# schematic.net
KiCad netlist of a schematic drawn in Altium Designer
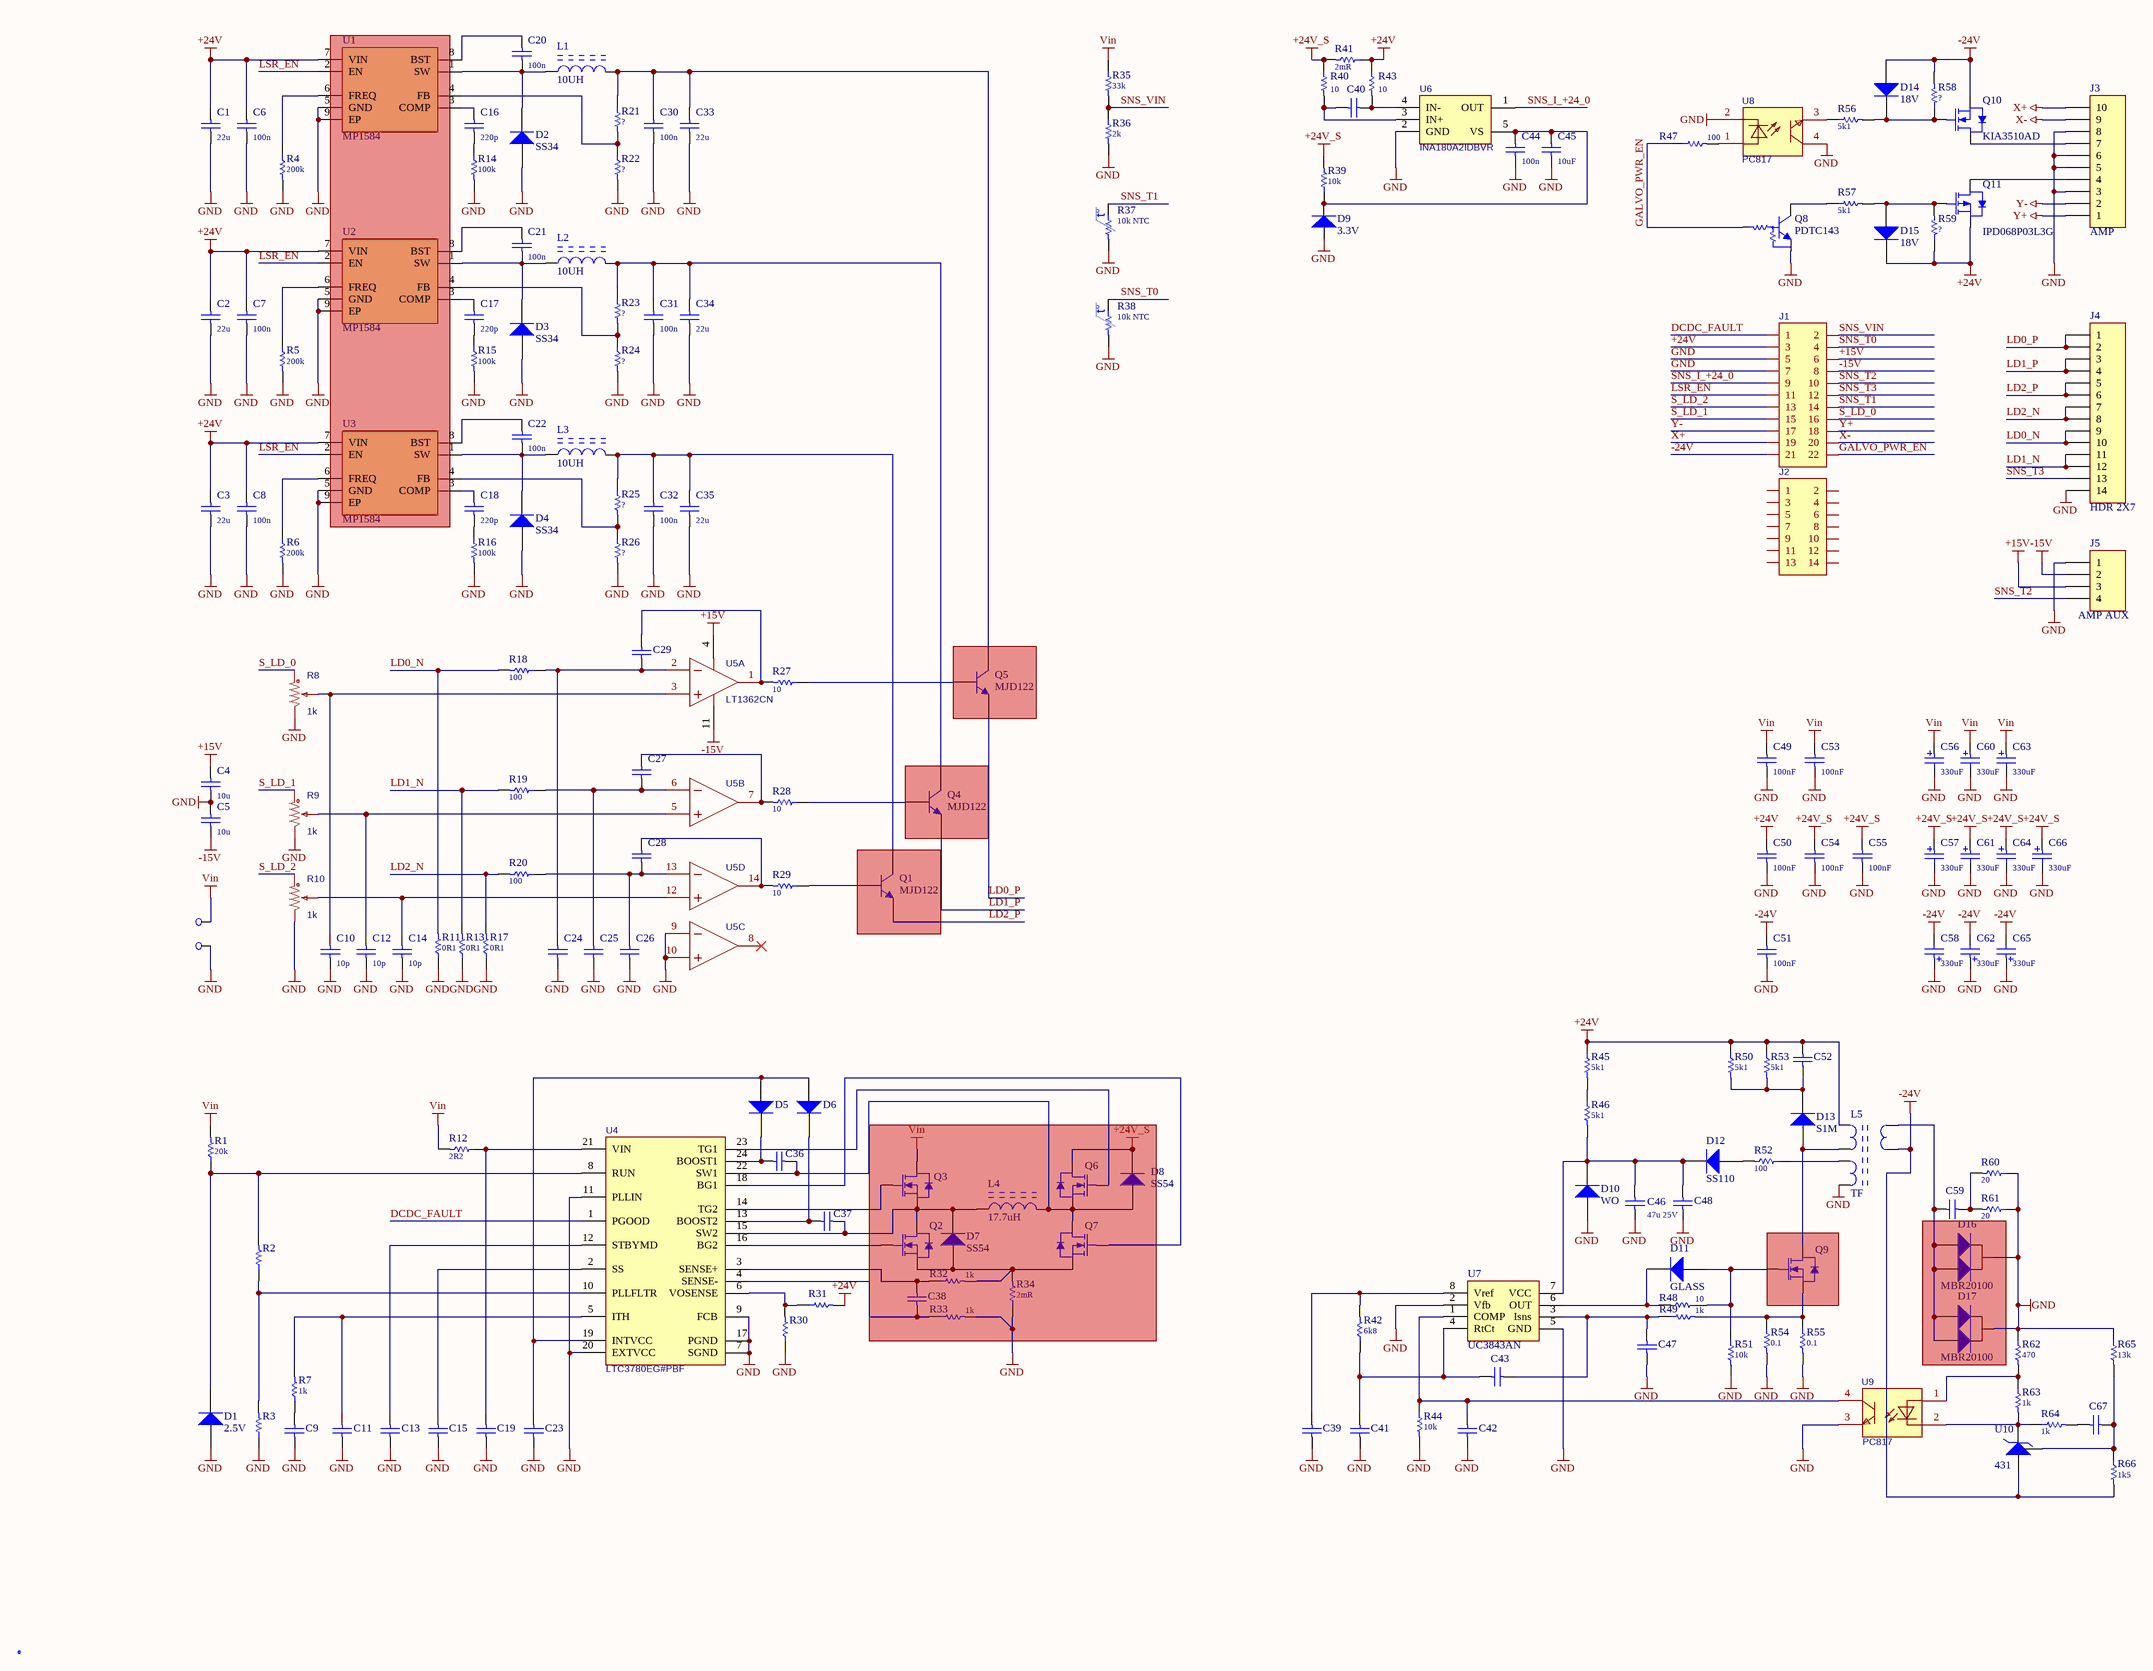
[diagram p0: schematic.SchDoc]

(export (version "E")
  (design (tool "Eeschema 10.0.6"))
  (components
    (comp (ref "C1") (value "22u") (footprint "C1210") (libsource (lib "Miscellaneous Devices") (part "CAP")))
    (comp (ref "C2") (value "22u") (footprint "C1210") (libsource (lib "Miscellaneous Devices") (part "CAP")))
    (comp (ref "C3") (value "22u") (footprint "C1210") (libsource (lib "Miscellaneous Devices") (part "CAP")))
    (comp (ref "C4")
      (value "10u")
      (footprint "C1210")
      (description "10u 1210")
      (libsource (lib "Miscellaneous Devices") (part "CAP"))
    )
    (comp (ref "C5")
      (value "10u")
      (footprint "C1210")
      (description "10u 1210")
      (libsource (lib "Miscellaneous Devices") (part "CAP"))
    )
    (comp (ref "C6")
      (value "100n")
      (footprint "C0603")
      (libsource (lib "Miscellaneous Devices") (part "CAP"))
    )
    (comp (ref "C7")
      (value "100n")
      (footprint "C0603")
      (libsource (lib "Miscellaneous Devices") (part "CAP"))
    )
    (comp (ref "C8")
      (value "100n")
      (footprint "C0603")
      (libsource (lib "Miscellaneous Devices") (part "CAP"))
    )
    (comp (ref "C9") (value "~") (footprint "C0805") (libsource (lib "Miscellaneous Devices") (part "CAP")))
    (comp (ref "C10")
      (value "10p")
      (footprint "C0402")
      (libsource (lib "Miscellaneous Devices") (part "CAP"))
    )
    (comp (ref "C11") (value "~") (footprint "C0805") (libsource (lib "Miscellaneous Devices") (part "CAP")))
    (comp (ref "C12")
      (value "10p")
      (footprint "C0402")
      (libsource (lib "Miscellaneous Devices") (part "CAP"))
    )
    (comp (ref "C13") (value "~") (footprint "C0805") (libsource (lib "Miscellaneous Devices") (part "CAP")))
    (comp (ref "C14")
      (value "10p")
      (footprint "C0402")
      (libsource (lib "Miscellaneous Devices") (part "CAP"))
    )
    (comp (ref "C15") (value "~") (footprint "C1206") (libsource (lib "Miscellaneous Devices") (part "CAP")))
    (comp (ref "C16")
      (value "220p")
      (footprint "C0603")
      (libsource (lib "Miscellaneous Devices") (part "CAP"))
    )
    (comp (ref "C17")
      (value "220p")
      (footprint "C0603")
      (libsource (lib "Miscellaneous Devices") (part "CAP"))
    )
    (comp (ref "C18")
      (value "220p")
      (footprint "C0603")
      (libsource (lib "Miscellaneous Devices") (part "CAP"))
    )
    (comp (ref "C19") (value "~") (footprint "C0805") (libsource (lib "Miscellaneous Devices") (part "CAP")))
    (comp (ref "C20")
      (value "100n")
      (footprint "C0603")
      (libsource (lib "Miscellaneous Devices") (part "CAP"))
    )
    (comp (ref "C21")
      (value "100n")
      (footprint "C0603")
      (libsource (lib "Miscellaneous Devices") (part "CAP"))
    )
    (comp (ref "C22")
      (value "100n")
      (footprint "C0603")
      (libsource (lib "Miscellaneous Devices") (part "CAP"))
    )
    (comp (ref "C23") (value "~") (footprint "C1206") (libsource (lib "Miscellaneous Devices") (part "CAP")))
    (comp (ref "C24")
      (value "10p")
      (footprint "C0402")
      (libsource (lib "Miscellaneous Devices") (part "CAP"))
    )
    (comp (ref "C25")
      (value "10p")
      (footprint "C0402")
      (libsource (lib "Miscellaneous Devices") (part "CAP"))
    )
    (comp (ref "C26")
      (value "10p")
      (footprint "C0402")
      (libsource (lib "Miscellaneous Devices") (part "CAP"))
    )
    (comp (ref "C27")
      (value "10p")
      (footprint "C0402")
      (libsource (lib "Miscellaneous Devices") (part "CAP"))
    )
    (comp (ref "C28")
      (value "10p")
      (footprint "C0402")
      (libsource (lib "Miscellaneous Devices") (part "CAP"))
    )
    (comp (ref "C29")
      (value "10p")
      (footprint "C0402")
      (libsource (lib "Miscellaneous Devices") (part "CAP"))
    )
    (comp (ref "C30")
      (value "100n")
      (footprint "C0603")
      (libsource (lib "Miscellaneous Devices") (part "CAP"))
    )
    (comp (ref "C31")
      (value "100n")
      (footprint "C0603")
      (libsource (lib "Miscellaneous Devices") (part "CAP"))
    )
    (comp (ref "C32")
      (value "100n")
      (footprint "C0603")
      (libsource (lib "Miscellaneous Devices") (part "CAP"))
    )
    (comp (ref "C33")
      (value "22u")
      (footprint "C1210")
      (libsource (lib "Miscellaneous Devices") (part "CAP"))
    )
    (comp (ref "C34")
      (value "22u")
      (footprint "C1210")
      (libsource (lib "Miscellaneous Devices") (part "CAP"))
    )
    (comp (ref "C35")
      (value "22u")
      (footprint "C1210")
      (libsource (lib "Miscellaneous Devices") (part "CAP"))
    )
    (comp (ref "C36") (value "~") (footprint "C0805") (libsource (lib "Miscellaneous Devices") (part "CAP")))
    (comp (ref "C37") (value "~") (footprint "C0805") (libsource (lib "Miscellaneous Devices") (part "CAP")))
    (comp (ref "C38") (value "~") (footprint "C0805") (libsource (lib "Miscellaneous Devices") (part "CAP")))
    (comp (ref "C39") (value "~") (footprint "C0805") (libsource (lib "Miscellaneous Devices") (part "CAP")))
    (comp (ref "C40") (value "~") (footprint "C0805") (libsource (lib "Miscellaneous Devices") (part "CAP")))
    (comp (ref "C41") (value "~") (footprint "C0805") (libsource (lib "Miscellaneous Devices") (part "CAP")))
    (comp (ref "C42") (value "~") (footprint "C0805") (libsource (lib "Miscellaneous Devices") (part "CAP")))
    (comp (ref "C43") (value "~") (footprint "C0805") (libsource (lib "Miscellaneous Devices") (part "CAP")))
    (comp (ref "C44")
      (value "100n")
      (footprint "C0603")
      (libsource (lib "Miscellaneous Devices") (part "CAP"))
    )
    (comp (ref "C45")
      (value "10uF")
      (footprint "C0805")
      (libsource (lib "Miscellaneous Devices") (part "CAP"))
    )
    (comp (ref "C46")
      (value "47u 25V")
      (footprint "C7343")
      (libsource (lib "Miscellaneous Devices") (part "CAP"))
    )
    (comp (ref "C47") (value "~") (footprint "C0805") (libsource (lib "Miscellaneous Devices") (part "CAP")))
    (comp (ref "C48") (value "~") (footprint "C0805") (libsource (lib "Miscellaneous Devices") (part "CAP")))
    (comp (ref "C49")
      (value "100nF")
      (footprint "C1210")
      (description "100nF 1210")
      (libsource (lib "Miscellaneous Devices") (part "CAP"))
    )
    (comp (ref "C50")
      (value "100nF")
      (footprint "C1210")
      (description "100nF 1210")
      (libsource (lib "Miscellaneous Devices") (part "CAP"))
    )
    (comp (ref "C51")
      (value "100nF")
      (footprint "C1210")
      (description "100nF 1210")
      (libsource (lib "Miscellaneous Devices") (part "CAP"))
    )
    (comp (ref "C52") (value "~") (footprint "C1206") (libsource (lib "Miscellaneous Devices") (part "CAP")))
    (comp (ref "C53")
      (value "100nF")
      (footprint "C1210")
      (description "100nF 1210")
      (libsource (lib "Miscellaneous Devices") (part "CAP"))
    )
    (comp (ref "C54")
      (value "100nF")
      (footprint "C1210")
      (description "100nF 1210")
      (libsource (lib "Miscellaneous Devices") (part "CAP"))
    )
    (comp (ref "C55")
      (value "100nF")
      (footprint "C1210")
      (description "100nF 1210")
      (libsource (lib "Miscellaneous Devices") (part "CAP"))
    )
    (comp (ref "C56")
      (value "330uF")
      (footprint "CAP-SMD_BD10.0-L10.3-W10.3-LS11.0-FD")
      (description "330uF 35V")
      (fields (field (name "LCSC PART NUMBER") "C2939792"))
      (libsource (lib "Miscellaneous Devices") (part "CAP_POL"))
    )
    (comp (ref "C57")
      (value "330uF")
      (footprint "CAP-SMD_BD10.0-L10.3-W10.3-LS11.0-FD")
      (description "330uF 35V")
      (fields (field (name "LCSC PART NUMBER") "C2939792"))
      (libsource (lib "Miscellaneous Devices") (part "CAP_POL"))
    )
    (comp (ref "C58")
      (value "330uF")
      (footprint "CAP-SMD_BD10.0-L10.3-W10.3-LS11.0-FD")
      (description "330uF 35V")
      (fields (field (name "LCSC PART NUMBER") "C2939792"))
      (libsource (lib "Miscellaneous Devices") (part "CAP_POL"))
    )
    (comp (ref "C59") (value "~") (footprint "C1206") (libsource (lib "Miscellaneous Devices") (part "CAP")))
    (comp (ref "C60")
      (value "330uF")
      (footprint "CAP-SMD_BD10.0-L10.3-W10.3-LS11.0-FD")
      (description "330uF 35V")
      (fields (field (name "LCSC PART NUMBER") "C2939792"))
      (libsource (lib "Miscellaneous Devices") (part "CAP_POL"))
    )
    (comp (ref "C61")
      (value "330uF")
      (footprint "CAP-SMD_BD10.0-L10.3-W10.3-LS11.0-FD")
      (description "330uF 35V")
      (fields (field (name "LCSC PART NUMBER") "C2939792"))
      (libsource (lib "Miscellaneous Devices") (part "CAP_POL"))
    )
    (comp (ref "C62")
      (value "330uF")
      (footprint "CAP-SMD_BD10.0-L10.3-W10.3-LS11.0-FD")
      (description "330uF 35V")
      (fields (field (name "LCSC PART NUMBER") "C2939792"))
      (libsource (lib "Miscellaneous Devices") (part "CAP_POL"))
    )
    (comp (ref "C63")
      (value "330uF")
      (footprint "CAP-SMD_BD10.0-L10.3-W10.3-LS11.0-FD")
      (description "330uF 35V")
      (fields (field (name "LCSC PART NUMBER") "C2939792"))
      (libsource (lib "Miscellaneous Devices") (part "CAP_POL"))
    )
    (comp (ref "C64")
      (value "330uF")
      (footprint "CAP-SMD_BD10.0-L10.3-W10.3-LS11.0-FD")
      (description "330uF 35V")
      (fields (field (name "LCSC PART NUMBER") "C2939792"))
      (libsource (lib "Miscellaneous Devices") (part "CAP_POL"))
    )
    (comp (ref "C65")
      (value "330uF")
      (footprint "CAP-SMD_BD10.0-L10.3-W10.3-LS11.0-FD")
      (description "330uF 35V")
      (fields (field (name "LCSC PART NUMBER") "C2939792"))
      (libsource (lib "Miscellaneous Devices") (part "CAP_POL"))
    )
    (comp (ref "C66")
      (value "330uF")
      (footprint "CAP-SMD_BD10.0-L10.3-W10.3-LS11.0-FD")
      (description "330uF 35V")
      (fields (field (name "LCSC PART NUMBER") "C2939792"))
      (libsource (lib "Miscellaneous Devices") (part "CAP_POL"))
    )
    (comp (ref "C67") (value "~") (footprint "C0805") (libsource (lib "Miscellaneous Devices") (part "CAP")))
    (comp (ref "D1")
      (value "2.5V")
      (footprint "sod-123")
      (fields (field (name "LCSC PART NUMBER") "C406712"))
      (libsource (lib "Miscellaneous Devices") (part "US1M-13-F"))
    )
    (comp (ref "D2")
      (value "SS34")
      (footprint "SMA")
      (libsource (lib "Miscellaneous Devices") (part "US1M-13-F"))
    )
    (comp (ref "D3")
      (value "SS34")
      (footprint "SMA")
      (libsource (lib "Miscellaneous Devices") (part "US1M-13-F"))
    )
    (comp (ref "D4")
      (value "SS34")
      (footprint "SMA")
      (libsource (lib "Miscellaneous Devices") (part "US1M-13-F"))
    )
    (comp (ref "D5")
      (value "~")
      (footprint "SOD-323")
      (libsource (lib "Miscellaneous Devices") (part "US1M-13-F"))
    )
    (comp (ref "D6")
      (value "~")
      (footprint "SOD-323")
      (libsource (lib "Miscellaneous Devices") (part "US1M-13-F"))
    )
    (comp (ref "D7")
      (value "SS54")
      (footprint "SMB")
      (libsource (lib "Miscellaneous Devices") (part "US1M-13-F"))
    )
    (comp (ref "D8")
      (value "SS54")
      (footprint "SMB")
      (libsource (lib "Miscellaneous Devices") (part "US1M-13-F"))
    )
    (comp (ref "D9")
      (value "3.3V")
      (footprint "sod-123")
      (fields (field (name "LCSC PART NUMBER") "C173413"))
      (libsource (lib "") (part "US1M-13-F_1"))
    )
    (comp (ref "D10")
      (value "WO")
      (footprint "SMA")
      (libsource (lib "Miscellaneous Devices") (part "US1M-13-F"))
    )
    (comp (ref "D11")
      (value "GLASS")
      (footprint "SMA")
      (libsource (lib "Miscellaneous Devices") (part "US1M-13-F"))
    )
    (comp (ref "D12")
      (value "SS110")
      (footprint "SMA")
      (libsource (lib "Miscellaneous Devices") (part "US1M-13-F"))
    )
    (comp (ref "D13")
      (value "S1M")
      (footprint "SMA")
      (libsource (lib "Miscellaneous Devices") (part "US1M-13-F"))
    )
    (comp (ref "D14")
      (value "18V")
      (footprint "SOD-123")
      (libsource (lib "Miscellaneous Devices") (part "US1M-13-F"))
    )
    (comp (ref "D15")
      (value "18V")
      (footprint "SOD-123")
      (libsource (lib "Miscellaneous Devices") (part "US1M-13-F"))
    )
    (comp (ref "D16") (value "MBR20100") (footprint "D2PAK") (libsource (lib "Schlib1") (part "MBR20100")))
    (comp (ref "D17") (value "MBR20100") (footprint "D2PAK") (libsource (lib "Schlib1") (part "MBR20100")))
    (comp (ref "DN1")
      (value "~")
      (footprint "PAD_CAST2_0.8MM")
      (libsource (lib "Schlib1") (part "dummy net"))
    )
    (comp (ref "DN2")
      (value "~")
      (footprint "PAD_CAST2_0.8MM")
      (libsource (lib "Schlib1") (part "dummy net"))
    )
    (comp (ref "J1") (value "~") (footprint "HDR-2X11-P2.00") (libsource (lib "Schlib1") (part "HDR 2X11")))
    (comp (ref "J2") (value "~") (footprint "HDR-2X7-P2.00") (libsource (lib "") (part "HDR 2X7_1")))
    (comp (ref "J3") (value "AMP") (footprint "HDR-1X10_2.54") (libsource (lib "Schlib1") (part "Header 3")))
    (comp (ref "J4")
      (value "HDR 2X7")
      (footprint "HDR-2X7-P2.00")
      (libsource (lib "Schlib1") (part "HDR 2X7"))
    )
    (comp (ref "J5")
      (value "AMP AUX")
      (footprint "HDR-2X2-P2.00")
      (libsource (lib "Schlib1") (part "Header 2"))
    )
    (comp (ref "L1")
      (value "10UH")
      (footprint "IND-SMD_L7.2-W6.6_GPSR07X0")
      (description "CYA0630-10UH")
      (libsource (lib "Miscellaneous Devices") (part "SRN3015-100M"))
    )
    (comp (ref "L2")
      (value "10UH")
      (footprint "IND-SMD_L7.2-W6.6_GPSR07X0")
      (description "CYA0630-10UH")
      (libsource (lib "Miscellaneous Devices") (part "SRN3015-100M"))
    )
    (comp (ref "L3")
      (value "10UH")
      (footprint "IND-SMD_L7.2-W6.6_GPSR07X0")
      (description "CYA0630-10UH")
      (libsource (lib "Miscellaneous Devices") (part "SRN3015-100M"))
    )
    (comp (ref "L4")
      (value "17.7uH")
      (footprint "IND_PWR_0")
      (description "17x10x7 RING 14 TURN")
      (libsource (lib "Miscellaneous Devices") (part "7443551331"))
    )
    (comp (ref "L5") (value "TF") (footprint "TRANS_0") (libsource (lib "Schlib1") (part "7443551331")))
    (comp (ref "LOGO1") (value "LOGO") (footprint "LOGO") (libsource (lib "Schlib1") (part "LOGO")))
    (comp (ref "Q1")
      (value "MJD122")
      (footprint "TO-252AA (DPAK)")
      (libsource (lib "Miscellaneous Devices") (part "MMBT2222ALT1G"))
    )
    (comp (ref "Q2")
      (value "AOD4184")
      (footprint "TO-252AA (DPAK)")
      (libsource (lib "Miscellaneous Devices") (part "2N7002"))
    )
    (comp (ref "Q3")
      (value "AOD4184")
      (footprint "TO-252AA (DPAK)")
      (libsource (lib "Miscellaneous Devices") (part "2N7002"))
    )
    (comp (ref "Q4")
      (value "MJD122")
      (footprint "TO-252AA (DPAK)")
      (libsource (lib "Miscellaneous Devices") (part "MMBT2222ALT1G"))
    )
    (comp (ref "Q5")
      (value "MJD122")
      (footprint "TO-252AA (DPAK)")
      (libsource (lib "Miscellaneous Devices") (part "MMBT2222ALT1G"))
    )
    (comp (ref "Q6")
      (value "AOD4184")
      (footprint "TO-252AA (DPAK)")
      (libsource (lib "Miscellaneous Devices") (part "2N7002"))
    )
    (comp (ref "Q7")
      (value "AOD4184")
      (footprint "TO-252AA (DPAK)")
      (libsource (lib "Miscellaneous Devices") (part "2N7002"))
    )
    (comp (ref "Q8")
      (value "PDTC143")
      (footprint "SOT-23")
      (description "PDTC143XT,215")
      (fields (field (name "LCSC PART NUMBER") "C183011"))
      (libsource (lib "") (part "MMBT2222ALT1G_1"))
    )
    (comp (ref "Q9")
      (value "MDP1991")
      (footprint "D2PAK")
      (libsource (lib "Miscellaneous Devices") (part "2N7002"))
    )
    (comp (ref "Q10")
      (value "KIA3510AD")
      (footprint "TO-252AA (DPAK)")
      (description "AOD4184")
      (libsource (lib "Miscellaneous Devices") (part "2N7002"))
    )
    (comp (ref "Q11")
      (value "IPD068P03L3G")
      (footprint "TO-252AA (DPAK)")
      (libsource (lib "") (part "2N7002_1"))
    )
    (comp (ref "R1") (value "20k") (footprint "R0805") (libsource (lib "Miscellaneous Devices") (part "RES")))
    (comp (ref "R2") (value "~") (footprint "R0805") (libsource (lib "Miscellaneous Devices") (part "RES")))
    (comp (ref "R3") (value "~") (footprint "R0805") (libsource (lib "Miscellaneous Devices") (part "RES")))
    (comp (ref "R4")
      (value "200k")
      (footprint "R0603")
      (libsource (lib "Miscellaneous Devices") (part "RES"))
    )
    (comp (ref "R5")
      (value "200k")
      (footprint "R0603")
      (libsource (lib "Miscellaneous Devices") (part "RES"))
    )
    (comp (ref "R6")
      (value "200k")
      (footprint "R0603")
      (libsource (lib "Miscellaneous Devices") (part "RES"))
    )
    (comp (ref "R7") (value "1k") (footprint "R0805") (libsource (lib "Miscellaneous Devices") (part "RES")))
    (comp (ref "R8")
      (value "1k")
      (footprint "RES-ADJ-TH_3P-L10.0-W10.0-P2.50-L")
      (libsource (lib "Schlib1") (part "10kΩ"))
    )
    (comp (ref "R9")
      (value "1k")
      (footprint "RES-ADJ-TH_3P-L10.0-W10.0-P2.50-L")
      (libsource (lib "Schlib1") (part "10kΩ"))
    )
    (comp (ref "R10")
      (value "1k")
      (footprint "RES-ADJ-TH_3P-L10.0-W10.0-P2.50-L")
      (libsource (lib "Schlib1") (part "10kΩ"))
    )
    (comp (ref "R11")
      (value "0R1")
      (footprint "R1206")
      (libsource (lib "Miscellaneous Devices") (part "RES"))
    )
    (comp (ref "R12")
      (value "2R2")
      (footprint "R0805")
      (libsource (lib "Miscellaneous Devices") (part "RES"))
    )
    (comp (ref "R13")
      (value "0R1")
      (footprint "R1206")
      (libsource (lib "Miscellaneous Devices") (part "RES"))
    )
    (comp (ref "R14")
      (value "100k")
      (footprint "R0603")
      (libsource (lib "Miscellaneous Devices") (part "RES"))
    )
    (comp (ref "R15")
      (value "100k")
      (footprint "R0603")
      (libsource (lib "Miscellaneous Devices") (part "RES"))
    )
    (comp (ref "R16")
      (value "100k")
      (footprint "R0603")
      (libsource (lib "Miscellaneous Devices") (part "RES"))
    )
    (comp (ref "R17")
      (value "0R1")
      (footprint "R1206")
      (libsource (lib "Miscellaneous Devices") (part "RES"))
    )
    (comp (ref "R18")
      (value "100")
      (footprint "R0402")
      (libsource (lib "Miscellaneous Devices") (part "RES"))
    )
    (comp (ref "R19")
      (value "100")
      (footprint "R0402")
      (libsource (lib "Miscellaneous Devices") (part "RES"))
    )
    (comp (ref "R20")
      (value "100")
      (footprint "R0402")
      (libsource (lib "Miscellaneous Devices") (part "RES"))
    )
    (comp (ref "R21") (value "?") (footprint "R0603") (libsource (lib "Miscellaneous Devices") (part "RES")))
    (comp (ref "R22") (value "?") (footprint "R0603") (libsource (lib "Miscellaneous Devices") (part "RES")))
    (comp (ref "R23") (value "?") (footprint "R0603") (libsource (lib "Miscellaneous Devices") (part "RES")))
    (comp (ref "R24") (value "?") (footprint "R0603") (libsource (lib "Miscellaneous Devices") (part "RES")))
    (comp (ref "R25") (value "?") (footprint "R0603") (libsource (lib "Miscellaneous Devices") (part "RES")))
    (comp (ref "R26") (value "?") (footprint "R0603") (libsource (lib "Miscellaneous Devices") (part "RES")))
    (comp (ref "R27") (value "10") (footprint "R0805") (libsource (lib "Miscellaneous Devices") (part "RES")))
    (comp (ref "R28") (value "10") (footprint "R0805") (libsource (lib "Miscellaneous Devices") (part "RES")))
    (comp (ref "R29") (value "10") (footprint "R0805") (libsource (lib "Miscellaneous Devices") (part "RES")))
    (comp (ref "R30") (value "~") (footprint "R0805") (libsource (lib "Miscellaneous Devices") (part "RES")))
    (comp (ref "R31") (value "~") (footprint "R0805") (libsource (lib "Miscellaneous Devices") (part "RES")))
    (comp (ref "R32") (value "1k") (footprint "R0805") (libsource (lib "Miscellaneous Devices") (part "RES")))
    (comp (ref "R33") (value "1k") (footprint "R0805") (libsource (lib "Miscellaneous Devices") (part "RES")))
    (comp (ref "R34")
      (value "2mR")
      (footprint "R2512-WIDE")
      (description "2mR shunt 2512")
      (fields (field (name "LCSC PART NUMBER") "C728320"))
      (libsource (lib "Miscellaneous Devices") (part "RES"))
    )
    (comp (ref "R35")
      (value "33k")
      (footprint "R0603")
      (libsource (lib "Miscellaneous Devices") (part "RES"))
    )
    (comp (ref "R36") (value "2k") (footprint "R0603") (libsource (lib "Miscellaneous Devices") (part "RES")))
    (comp (ref "R37")
      (value "10k NTC")
      (footprint "R0402")
      (description "10k NTC 3434 0402")
      (fields (field (name "LCSC PART NUMBER") "C700820"))
      (libsource (lib "") (part "RES_1"))
    )
    (comp (ref "R38")
      (value "10k NTC")
      (footprint "R0402")
      (description "10k NTC 3434 0402")
      (fields (field (name "LCSC PART NUMBER") "C700820"))
      (libsource (lib "") (part "RES_1"))
    )
    (comp (ref "R39")
      (value "10k")
      (footprint "R0805")
      (libsource (lib "Miscellaneous Devices") (part "RES"))
    )
    (comp (ref "R40") (value "10") (footprint "R0603") (libsource (lib "Miscellaneous Devices") (part "RES")))
    (comp (ref "R41")
      (value "2mR")
      (footprint "R2512-WIDE")
      (description "2mR shunt 2512")
      (fields (field (name "LCSC PART NUMBER") "C728320"))
      (libsource (lib "Miscellaneous Devices") (part "RES"))
    )
    (comp (ref "R42")
      (value "6k8")
      (footprint "R0805")
      (libsource (lib "Miscellaneous Devices") (part "RES"))
    )
    (comp (ref "R43") (value "10") (footprint "R0603") (libsource (lib "Miscellaneous Devices") (part "RES")))
    (comp (ref "R44")
      (value "10k")
      (footprint "R0805")
      (libsource (lib "Miscellaneous Devices") (part "RES"))
    )
    (comp (ref "R45")
      (value "5k1")
      (footprint "R1206")
      (libsource (lib "Miscellaneous Devices") (part "RES"))
    )
    (comp (ref "R46")
      (value "5k1")
      (footprint "R1206")
      (libsource (lib "Miscellaneous Devices") (part "RES"))
    )
    (comp (ref "R47")
      (value "100")
      (footprint "R0603")
      (description "100 0603")
      (libsource (lib "Miscellaneous Devices") (part "RES"))
    )
    (comp (ref "R48") (value "10") (footprint "R0805") (libsource (lib "Miscellaneous Devices") (part "RES")))
    (comp (ref "R49") (value "1k") (footprint "R0805") (libsource (lib "Miscellaneous Devices") (part "RES")))
    (comp (ref "R50")
      (value "5k1")
      (footprint "R1206")
      (libsource (lib "Miscellaneous Devices") (part "RES"))
    )
    (comp (ref "R51")
      (value "10k")
      (footprint "R0805")
      (libsource (lib "Miscellaneous Devices") (part "RES"))
    )
    (comp (ref "R52")
      (value "100")
      (footprint "R1206")
      (libsource (lib "Miscellaneous Devices") (part "RES"))
    )
    (comp (ref "R53")
      (value "5k1")
      (footprint "R1206")
      (libsource (lib "Miscellaneous Devices") (part "RES"))
    )
    (comp (ref "R54")
      (value "0.1")
      (footprint "R1206")
      (libsource (lib "Miscellaneous Devices") (part "RES"))
    )
    (comp (ref "R55")
      (value "0.1")
      (footprint "R1206")
      (libsource (lib "Miscellaneous Devices") (part "RES"))
    )
    (comp (ref "R56")
      (value "5k1")
      (footprint "R0805")
      (libsource (lib "Miscellaneous Devices") (part "RES"))
    )
    (comp (ref "R57")
      (value "5k1")
      (footprint "R0805")
      (libsource (lib "Miscellaneous Devices") (part "RES"))
    )
    (comp (ref "R58") (value "?") (footprint "R0805") (libsource (lib "Miscellaneous Devices") (part "RES")))
    (comp (ref "R59") (value "?") (footprint "R0805") (libsource (lib "Miscellaneous Devices") (part "RES")))
    (comp (ref "R60") (value "20") (footprint "R1206") (libsource (lib "Miscellaneous Devices") (part "RES")))
    (comp (ref "R61") (value "20") (footprint "R1206") (libsource (lib "Miscellaneous Devices") (part "RES")))
    (comp (ref "R62")
      (value "470")
      (footprint "R0805")
      (libsource (lib "Miscellaneous Devices") (part "RES"))
    )
    (comp (ref "R63") (value "1k") (footprint "R0805") (libsource (lib "Miscellaneous Devices") (part "RES")))
    (comp (ref "R64") (value "1k") (footprint "R0805") (libsource (lib "Miscellaneous Devices") (part "RES")))
    (comp (ref "R65")
      (value "13k")
      (footprint "R0805")
      (libsource (lib "Miscellaneous Devices") (part "RES"))
    )
    (comp (ref "R66")
      (value "1k5")
      (footprint "R0805")
      (libsource (lib "Miscellaneous Devices") (part "RES"))
    )
    (comp (ref "U1") (value "MP1584") (footprint "PowerSOIC-8") (libsource (lib "Schlib1") (part "MP1584")))
    (comp (ref "U2") (value "MP1584") (footprint "PowerSOIC-8") (libsource (lib "Schlib1") (part "MP1584")))
    (comp (ref "U3") (value "MP1584") (footprint "PowerSOIC-8") (libsource (lib "Schlib1") (part "MP1584")))
    (comp (ref "U4")
      (value "LTC3780EG#PBF")
      (footprint "SSOP-24")
      (libsource (lib "Schlib1") (part "LTC3780EG#PBF"))
    )
    (comp (ref "U5")
      (value "LT1362CN")
      (footprint "DIP-14")
      (libsource (lib "Schlib1") (part "LT1362CS#PBF"))
    )
    (comp (ref "U6")
      (value "INA180A2IDBVR")
      (footprint "SOT-23-5")
      (libsource (lib "Schlib1") (part "INA180A2IDBVR"))
    )
    (comp (ref "U7") (value "UC3843AN") (footprint "SO-8") (libsource (lib "Schlib1") (part "UC3843AN")))
    (comp (ref "U8") (value "PC817") (footprint "SMD-4") (libsource (lib "") (part "PC817C_C3025164_1")))
    (comp (ref "U9") (value "PC817") (footprint "SMD-4") (libsource (lib "Schlib1") (part "PC817C_C3025164")))
    (comp (ref "U10") (value "431") (footprint "SOT-23") (libsource (lib "Schlib1") (part "NCP51460SN33T1G")))
  )
  (nets
    (net (code "1") (name "+15V") (class "Default")
      (node (ref "C4") (pin "2") (pinfunction "2_2") (pintype "passive"))
      (node (ref "J1") (pin "6") (pinfunction "6_6") (pintype "passive"))
      (node (ref "J5") (pin "3") (pinfunction "3_3") (pintype "passive"))
      (node (ref "U5") (pin "4") (pinfunction "V+_4") (pintype "passive"))
    )
    (net (code "2") (name "+24V") (class "Default")
      (node (ref "C1") (pin "2") (pinfunction "2_2") (pintype "passive"))
      (node (ref "C2") (pin "2") (pinfunction "2_2") (pintype "passive"))
      (node (ref "C3") (pin "2") (pinfunction "2_2") (pintype "passive"))
      (node (ref "C50") (pin "2") (pinfunction "2_2") (pintype "passive"))
      (node (ref "C52") (pin "1") (pinfunction "1_1") (pintype "passive"))
      (node (ref "C6") (pin "2") (pinfunction "2_2") (pintype "passive"))
      (node (ref "C7") (pin "2") (pinfunction "2_2") (pintype "passive"))
      (node (ref "C8") (pin "2") (pinfunction "2_2") (pintype "passive"))
      (node (ref "D15") (pin "2") (pinfunction "K_2") (pintype "passive"))
      (node (ref "J1") (pin "3") (pinfunction "3_3") (pintype "passive"))
      (node (ref "L5") (pin "1") (pinfunction "1_1") (pintype "passive"))
      (node (ref "Q11") (pin "3") (pinfunction "SOURCE_3") (pintype "passive"))
      (node (ref "R31") (pin "2") (pinfunction "2_2") (pintype "passive"))
      (node (ref "R41") (pin "1") (pinfunction "1_1") (pintype "passive"))
      (node (ref "R43") (pin "1") (pinfunction "1_1") (pintype "passive"))
      (node (ref "R45") (pin "1") (pinfunction "1_1") (pintype "passive"))
      (node (ref "R50") (pin "1") (pinfunction "1_1") (pintype "passive"))
      (node (ref "R53") (pin "1") (pinfunction "1_1") (pintype "passive"))
      (node (ref "R59") (pin "1") (pinfunction "1_1") (pintype "passive"))
      (node (ref "U1") (pin "7") (pinfunction "VIN_7") (pintype "passive"))
      (node (ref "U2") (pin "7") (pinfunction "VIN_7") (pintype "passive"))
      (node (ref "U3") (pin "7") (pinfunction "VIN_7") (pintype "passive"))
    )
    (net (code "3") (name "+24V_S") (class "Default")
      (node (ref "C54") (pin "2") (pinfunction "2_2") (pintype "passive"))
      (node (ref "C55") (pin "2") (pinfunction "2_2") (pintype "passive"))
      (node (ref "C57") (pin "1") (pinfunction "1_1") (pintype "passive"))
      (node (ref "C61") (pin "1") (pinfunction "1_1") (pintype "passive"))
      (node (ref "C64") (pin "1") (pinfunction "1_1") (pintype "passive"))
      (node (ref "C66") (pin "1") (pinfunction "1_1") (pintype "passive"))
      (node (ref "D8") (pin "2") (pinfunction "K_2") (pintype "passive"))
      (node (ref "Q6") (pin "2") (pinfunction "DRAIN_2") (pintype "passive"))
      (node (ref "R39") (pin "2") (pinfunction "2_2") (pintype "passive"))
      (node (ref "R40") (pin "1") (pinfunction "1_1") (pintype "passive"))
      (node (ref "R41") (pin "2") (pinfunction "2_2") (pintype "passive"))
    )
    (net (code "4") (name "-15V") (class "Default")
      (node (ref "C5") (pin "1") (pinfunction "1_1") (pintype "passive"))
      (node (ref "J1") (pin "8") (pinfunction "8_8") (pintype "passive"))
      (node (ref "J5") (pin "2") (pinfunction "2_2") (pintype "passive"))
      (node (ref "U5") (pin "11") (pinfunction "V-_11") (pintype "passive"))
    )
    (net (code "5") (name "-24V") (class "Default")
      (node (ref "C51") (pin "2") (pinfunction "2_2") (pintype "passive"))
      (node (ref "C58") (pin "2") (pinfunction "2_2") (pintype "passive"))
      (node (ref "C62") (pin "2") (pinfunction "2_2") (pintype "passive"))
      (node (ref "C65") (pin "2") (pinfunction "2_2") (pintype "passive"))
      (node (ref "D14") (pin "1") (pinfunction "A_1") (pintype "passive"))
      (node (ref "J1") (pin "21") (pinfunction "21_21") (pintype "passive"))
      (node (ref "L5") (pin "5") (pinfunction "5_5") (pintype "passive"))
      (node (ref "Q10") (pin "3") (pinfunction "SOURCE_3") (pintype "passive"))
      (node (ref "R58") (pin "2") (pinfunction "2_2") (pintype "passive"))
      (node (ref "R66") (pin "2") (pinfunction "2_2") (pintype "passive"))
      (node (ref "U10") (pin "3") (pinfunction "A_3") (pintype "passive"))
    )
    (net (code "6") (name "/DCDC_FAULT") (class "Default")
      (node (ref "J1") (pin "1") (pinfunction "1_1") (pintype "passive"))
      (node (ref "U4") (pin "1") (pinfunction "PGOOD_1") (pintype "passive"))
    )
    (net (code "7") (name "/GALVO_PWR_EN") (class "Default")
      (node (ref "J1") (pin "22") (pinfunction "22_22") (pintype "passive"))
      (node (ref "Q8") (pin "1") (pinfunction "B_1") (pintype "passive"))
      (node (ref "R47") (pin "1") (pinfunction "1_1") (pintype "passive"))
    )
    (net (code "8") (name "/LD0_N") (class "Default")
      (node (ref "J4") (pin "10") (pinfunction "10_10") (pintype "passive"))
      (node (ref "J4") (pin "9") (pinfunction "9_9") (pintype "passive"))
      (node (ref "R11") (pin "2") (pinfunction "2_2") (pintype "passive"))
      (node (ref "R18") (pin "2") (pinfunction "2_2") (pintype "passive"))
    )
    (net (code "9") (name "/LD0_P") (class "Default")
      (node (ref "J4") (pin "1") (pinfunction "1_1") (pintype "passive"))
      (node (ref "J4") (pin "2") (pinfunction "2_2") (pintype "passive"))
      (node (ref "Q5") (pin "3") (pinfunction "E_3") (pintype "passive"))
    )
    (net (code "10") (name "/LD1_N") (class "Default")
      (node (ref "J4") (pin "11") (pinfunction "11_11") (pintype "passive"))
      (node (ref "J4") (pin "12") (pinfunction "12_12") (pintype "passive"))
      (node (ref "R13") (pin "2") (pinfunction "2_2") (pintype "passive"))
      (node (ref "R19") (pin "2") (pinfunction "2_2") (pintype "passive"))
    )
    (net (code "11") (name "/LD1_P") (class "Default")
      (node (ref "J4") (pin "3") (pinfunction "3_3") (pintype "passive"))
      (node (ref "J4") (pin "4") (pinfunction "4_4") (pintype "passive"))
      (node (ref "Q4") (pin "3") (pinfunction "E_3") (pintype "passive"))
    )
    (net (code "12") (name "/LD2_N") (class "Default")
      (node (ref "J4") (pin "7") (pinfunction "7_7") (pintype "passive"))
      (node (ref "J4") (pin "8") (pinfunction "8_8") (pintype "passive"))
      (node (ref "R17") (pin "2") (pinfunction "2_2") (pintype "passive"))
      (node (ref "R20") (pin "2") (pinfunction "2_2") (pintype "passive"))
    )
    (net (code "13") (name "/LD2_P") (class "Default")
      (node (ref "J4") (pin "5") (pinfunction "5_5") (pintype "passive"))
      (node (ref "J4") (pin "6") (pinfunction "6_6") (pintype "passive"))
      (node (ref "Q1") (pin "3") (pinfunction "E_3") (pintype "passive"))
    )
    (net (code "14") (name "/LSR_EN") (class "Default")
      (node (ref "J1") (pin "11") (pinfunction "11_11") (pintype "passive"))
      (node (ref "U1") (pin "2") (pinfunction "EN_2") (pintype "passive"))
      (node (ref "U2") (pin "2") (pinfunction "EN_2") (pintype "passive"))
      (node (ref "U3") (pin "2") (pinfunction "EN_2") (pintype "passive"))
    )
    (net (code "15") (name "/SNS_I_+24_0") (class "Default")
      (node (ref "J1") (pin "9") (pinfunction "9_9") (pintype "passive"))
      (node (ref "U6") (pin "1") (pinfunction "OUT_1") (pintype "passive"))
    )
    (net (code "16") (name "/SNS_T0") (class "Default")
      (node (ref "J1") (pin "4") (pinfunction "4_4") (pintype "passive"))
      (node (ref "R38") (pin "1") (pinfunction "1_1") (pintype "passive"))
    )
    (net (code "17") (name "/SNS_T1") (class "Default")
      (node (ref "J1") (pin "14") (pinfunction "14_14") (pintype "passive"))
      (node (ref "R37") (pin "1") (pinfunction "1_1") (pintype "passive"))
    )
    (net (code "18") (name "/SNS_T2") (class "Default")
      (node (ref "J1") (pin "10") (pinfunction "10_10") (pintype "passive"))
      (node (ref "J5") (pin "4") (pinfunction "4_4") (pintype "passive"))
    )
    (net (code "19") (name "/SNS_T3") (class "Default")
      (node (ref "J1") (pin "12") (pinfunction "12_12") (pintype "passive"))
      (node (ref "J4") (pin "13") (pinfunction "13_13") (pintype "passive"))
    )
    (net (code "20") (name "/SNS_VIN") (class "Default")
      (node (ref "J1") (pin "2") (pinfunction "2_2") (pintype "passive"))
      (node (ref "R35") (pin "2") (pinfunction "2_2") (pintype "passive"))
      (node (ref "R36") (pin "1") (pinfunction "1_1") (pintype "passive"))
    )
    (net (code "21") (name "/S_LD_0") (class "Default")
      (node (ref "J1") (pin "16") (pinfunction "16_16") (pintype "passive"))
      (node (ref "R8") (pin "1") (pinfunction "1_1") (pintype "passive"))
    )
    (net (code "22") (name "/S_LD_1") (class "Default")
      (node (ref "J1") (pin "15") (pinfunction "15_15") (pintype "passive"))
      (node (ref "R9") (pin "1") (pinfunction "1_1") (pintype "passive"))
    )
    (net (code "23") (name "/S_LD_2") (class "Default")
      (node (ref "J1") (pin "13") (pinfunction "13_13") (pintype "passive"))
      (node (ref "R10") (pin "1") (pinfunction "1_1") (pintype "passive"))
    )
    (net (code "24") (name "GND") (class "Default")
      (node (ref "C1") (pin "1") (pinfunction "1_1") (pintype "passive"))
      (node (ref "C10") (pin "1") (pinfunction "1_1") (pintype "passive"))
      (node (ref "C11") (pin "2") (pinfunction "2_2") (pintype "passive"))
      (node (ref "C12") (pin "1") (pinfunction "1_1") (pintype "passive"))
      (node (ref "C13") (pin "2") (pinfunction "2_2") (pintype "passive"))
      (node (ref "C14") (pin "1") (pinfunction "1_1") (pintype "passive"))
      (node (ref "C15") (pin "2") (pinfunction "2_2") (pintype "passive"))
      (node (ref "C19") (pin "2") (pinfunction "2_2") (pintype "passive"))
      (node (ref "C2") (pin "1") (pinfunction "1_1") (pintype "passive"))
      (node (ref "C23") (pin "2") (pinfunction "2_2") (pintype "passive"))
      (node (ref "C24") (pin "1") (pinfunction "1_1") (pintype "passive"))
      (node (ref "C25") (pin "1") (pinfunction "1_1") (pintype "passive"))
      (node (ref "C26") (pin "1") (pinfunction "1_1") (pintype "passive"))
      (node (ref "C3") (pin "1") (pinfunction "1_1") (pintype "passive"))
      (node (ref "C30") (pin "1") (pinfunction "1_1") (pintype "passive"))
      (node (ref "C31") (pin "1") (pinfunction "1_1") (pintype "passive"))
      (node (ref "C32") (pin "1") (pinfunction "1_1") (pintype "passive"))
      (node (ref "C33") (pin "1") (pinfunction "1_1") (pintype "passive"))
      (node (ref "C34") (pin "1") (pinfunction "1_1") (pintype "passive"))
      (node (ref "C35") (pin "1") (pinfunction "1_1") (pintype "passive"))
      (node (ref "C39") (pin "2") (pinfunction "2_2") (pintype "passive"))
      (node (ref "C4") (pin "1") (pinfunction "1_1") (pintype "passive"))
      (node (ref "C41") (pin "2") (pinfunction "2_2") (pintype "passive"))
      (node (ref "C42") (pin "1") (pinfunction "1_1") (pintype "passive"))
      (node (ref "C44") (pin "1") (pinfunction "1_1") (pintype "passive"))
      (node (ref "C45") (pin "1") (pinfunction "1_1") (pintype "passive"))
      (node (ref "C46") (pin "2") (pinfunction "2_2") (pintype "passive"))
      (node (ref "C47") (pin "2") (pinfunction "2_2") (pintype "passive"))
      (node (ref "C48") (pin "2") (pinfunction "2_2") (pintype "passive"))
      (node (ref "C49") (pin "1") (pinfunction "1_1") (pintype "passive"))
      (node (ref "C5") (pin "2") (pinfunction "2_2") (pintype "passive"))
      (node (ref "C50") (pin "1") (pinfunction "1_1") (pintype "passive"))
      (node (ref "C51") (pin "1") (pinfunction "1_1") (pintype "passive"))
      (node (ref "C53") (pin "1") (pinfunction "1_1") (pintype "passive"))
      (node (ref "C54") (pin "1") (pinfunction "1_1") (pintype "passive"))
      (node (ref "C55") (pin "1") (pinfunction "1_1") (pintype "passive"))
      (node (ref "C56") (pin "2") (pinfunction "2_2") (pintype "passive"))
      (node (ref "C57") (pin "2") (pinfunction "2_2") (pintype "passive"))
      (node (ref "C58") (pin "1") (pinfunction "1_1") (pintype "passive"))
      (node (ref "C6") (pin "1") (pinfunction "1_1") (pintype "passive"))
      (node (ref "C60") (pin "2") (pinfunction "2_2") (pintype "passive"))
      (node (ref "C61") (pin "2") (pinfunction "2_2") (pintype "passive"))
      (node (ref "C62") (pin "1") (pinfunction "1_1") (pintype "passive"))
      (node (ref "C63") (pin "2") (pinfunction "2_2") (pintype "passive"))
      (node (ref "C64") (pin "2") (pinfunction "2_2") (pintype "passive"))
      (node (ref "C65") (pin "1") (pinfunction "1_1") (pintype "passive"))
      (node (ref "C66") (pin "2") (pinfunction "2_2") (pintype "passive"))
      (node (ref "C7") (pin "1") (pinfunction "1_1") (pintype "passive"))
      (node (ref "C8") (pin "1") (pinfunction "1_1") (pintype "passive"))
      (node (ref "C9") (pin "2") (pinfunction "2_2") (pintype "passive"))
      (node (ref "D1") (pin "1") (pinfunction "A_1") (pintype "passive"))
      (node (ref "D10") (pin "1") (pinfunction "A_1") (pintype "passive"))
      (node (ref "D16") (pin "2") (pinfunction "A_2") (pintype "passive"))
      (node (ref "D17") (pin "2") (pinfunction "A_2") (pintype "passive"))
      (node (ref "D2") (pin "1") (pinfunction "A_1") (pintype "passive"))
      (node (ref "D3") (pin "1") (pinfunction "A_1") (pintype "passive"))
      (node (ref "D4") (pin "1") (pinfunction "A_1") (pintype "passive"))
      (node (ref "D9") (pin "1") (pinfunction "A_1") (pintype "passive"))
      (node (ref "DN2") (pin "1") (pinfunction "1_1") (pintype "passive"))
      (node (ref "J1") (pin "5") (pinfunction "5_5") (pintype "passive"))
      (node (ref "J1") (pin "7") (pinfunction "7_7") (pintype "passive"))
      (node (ref "J3") (pin "3") (pinfunction "3_3") (pintype "passive"))
      (node (ref "J3") (pin "5") (pinfunction "5_5") (pintype "passive"))
      (node (ref "J3") (pin "6") (pinfunction "6_6") (pintype "passive"))
      (node (ref "J3") (pin "8") (pinfunction "8_8") (pintype "passive"))
      (node (ref "J4") (pin "14") (pinfunction "14_14") (pintype "passive"))
      (node (ref "J5") (pin "1") (pinfunction "1_1") (pintype "passive"))
      (node (ref "L5") (pin "3") (pinfunction "3_3") (pintype "passive"))
      (node (ref "Q8") (pin "2") (pinfunction "E_2") (pintype "passive"))
      (node (ref "R10") (pin "3") (pinfunction "3_3") (pintype "passive"))
      (node (ref "R11") (pin "1") (pinfunction "1_1") (pintype "passive"))
      (node (ref "R13") (pin "1") (pinfunction "1_1") (pintype "passive"))
      (node (ref "R14") (pin "2") (pinfunction "2_2") (pintype "passive"))
      (node (ref "R15") (pin "2") (pinfunction "2_2") (pintype "passive"))
      (node (ref "R16") (pin "2") (pinfunction "2_2") (pintype "passive"))
      (node (ref "R17") (pin "1") (pinfunction "1_1") (pintype "passive"))
      (node (ref "R22") (pin "2") (pinfunction "2_2") (pintype "passive"))
      (node (ref "R24") (pin "2") (pinfunction "2_2") (pintype "passive"))
      (node (ref "R26") (pin "2") (pinfunction "2_2") (pintype "passive"))
      (node (ref "R3") (pin "1") (pinfunction "1_1") (pintype "passive"))
      (node (ref "R30") (pin "1") (pinfunction "1_1") (pintype "passive"))
      (node (ref "R33") (pin "2") (pinfunction "2_2") (pintype "passive"))
      (node (ref "R34") (pin "1") (pinfunction "1_1") (pintype "passive"))
      (node (ref "R36") (pin "2") (pinfunction "2_2") (pintype "passive"))
      (node (ref "R37") (pin "2") (pinfunction "2_2") (pintype "passive"))
      (node (ref "R38") (pin "2") (pinfunction "2_2") (pintype "passive"))
      (node (ref "R4") (pin "2") (pinfunction "2_2") (pintype "passive"))
      (node (ref "R44") (pin "2") (pinfunction "2_2") (pintype "passive"))
      (node (ref "R5") (pin "2") (pinfunction "2_2") (pintype "passive"))
      (node (ref "R51") (pin "2") (pinfunction "2_2") (pintype "passive"))
      (node (ref "R54") (pin "2") (pinfunction "2_2") (pintype "passive"))
      (node (ref "R55") (pin "2") (pinfunction "2_2") (pintype "passive"))
      (node (ref "R6") (pin "2") (pinfunction "2_2") (pintype "passive"))
      (node (ref "R60") (pin "1") (pinfunction "1_1") (pintype "passive"))
      (node (ref "R61") (pin "1") (pinfunction "1_1") (pintype "passive"))
      (node (ref "R62") (pin "1") (pinfunction "1_1") (pintype "passive"))
      (node (ref "R65") (pin "1") (pinfunction "1_1") (pintype "passive"))
      (node (ref "R8") (pin "3") (pinfunction "3_3") (pintype "passive"))
      (node (ref "R9") (pin "3") (pinfunction "3_3") (pintype "passive"))
      (node (ref "U1") (pin "5") (pinfunction "GND_5") (pintype "passive"))
      (node (ref "U1") (pin "9") (pinfunction "EP_9") (pintype "passive"))
      (node (ref "U2") (pin "5") (pinfunction "GND_5") (pintype "passive"))
      (node (ref "U2") (pin "9") (pinfunction "EP_9") (pintype "passive"))
      (node (ref "U3") (pin "5") (pinfunction "GND_5") (pintype "passive"))
      (node (ref "U3") (pin "9") (pinfunction "EP_9") (pintype "passive"))
      (node (ref "U4") (pin "11") (pinfunction "PLLIN_11") (pintype "passive"))
      (node (ref "U4") (pin "17") (pinfunction "PGND_17") (pintype "passive"))
      (node (ref "U4") (pin "20") (pinfunction "EXTVCC_20") (pintype "passive"))
      (node (ref "U4") (pin "7") (pinfunction "SGND_7") (pintype "passive"))
      (node (ref "U4") (pin "9") (pinfunction "FCB_9") (pintype "passive"))
      (node (ref "U5") (pin "10") (pinfunction "INC+_10") (pintype "passive"))
      (node (ref "U5") (pin "9") (pinfunction "INC-_9") (pintype "passive"))
      (node (ref "U6") (pin "2") (pinfunction "GND_2") (pintype "passive"))
      (node (ref "U7") (pin "2") (pinfunction "Vfb_2") (pintype "passive"))
      (node (ref "U7") (pin "5") (pinfunction "GND_5") (pintype "passive"))
      (node (ref "U8") (pin "2") (pinfunction "2_2") (pintype "passive"))
      (node (ref "U8") (pin "4") (pinfunction "4_4") (pintype "passive"))
      (node (ref "U9") (pin "3") (pinfunction "3_3") (pintype "passive"))
    )
    (net (code "25") (name "Net-(C9-Pad1)") (class "Default")
      (node (ref "C9") (pin "1") (pinfunction "1_1") (pintype "passive"))
      (node (ref "R7") (pin "1") (pinfunction "1_1") (pintype "passive"))
    )
    (net (code "26") (name "Net-(C16-Pad1)") (class "Default")
      (node (ref "C16") (pin "1") (pinfunction "1_1") (pintype "passive"))
      (node (ref "R14") (pin "1") (pinfunction "1_1") (pintype "passive"))
    )
    (net (code "27") (name "Net-(C17-Pad1)") (class "Default")
      (node (ref "C17") (pin "1") (pinfunction "1_1") (pintype "passive"))
      (node (ref "R15") (pin "1") (pinfunction "1_1") (pintype "passive"))
    )
    (net (code "28") (name "Net-(C18-Pad1)") (class "Default")
      (node (ref "C18") (pin "1") (pinfunction "1_1") (pintype "passive"))
      (node (ref "R16") (pin "1") (pinfunction "1_1") (pintype "passive"))
    )
    (net (code "29") (name "Net-(C59-Pad1)") (class "Default")
      (node (ref "C59") (pin "1") (pinfunction "1_1") (pintype "passive"))
      (node (ref "R60") (pin "2") (pinfunction "2_2") (pintype "passive"))
      (node (ref "R61") (pin "2") (pinfunction "2_2") (pintype "passive"))
    )
    (net (code "30") (name "Net-(C59-Pad2)") (class "Default")
      (node (ref "C59") (pin "2") (pinfunction "2_2") (pintype "passive"))
      (node (ref "D16") (pin "1") (pinfunction "K_1") (pintype "passive"))
      (node (ref "D16") (pin "3") (pinfunction "K_3") (pintype "passive"))
      (node (ref "D17") (pin "1") (pinfunction "K_1") (pintype "passive"))
      (node (ref "D17") (pin "3") (pinfunction "K_3") (pintype "passive"))
      (node (ref "L5") (pin "6") (pinfunction "6_6") (pintype "passive"))
    )
    (net (code "31") (name "Net-(C67-Pad2)") (class "Default")
      (node (ref "C67") (pin "2") (pinfunction "2_2") (pintype "passive"))
      (node (ref "R64") (pin "2") (pinfunction "2_2") (pintype "passive"))
    )
    (net (code "32") (name "Net-(D1-K)") (class "Default")
      (node (ref "D1") (pin "2") (pinfunction "K_2") (pintype "passive"))
      (node (ref "R1") (pin "1") (pinfunction "1_1") (pintype "passive"))
      (node (ref "R2") (pin "2") (pinfunction "2_2") (pintype "passive"))
      (node (ref "U4") (pin "8") (pinfunction "RUN_8") (pintype "passive"))
    )
    (net (code "33") (name "Net-(D2-K)") (class "Default")
      (node (ref "C20") (pin "1") (pinfunction "1_1") (pintype "passive"))
      (node (ref "D2") (pin "2") (pinfunction "K_2") (pintype "passive"))
      (node (ref "L1") (pin "1") (pinfunction "1_1") (pintype "passive"))
      (node (ref "U1") (pin "1") (pinfunction "SW_1") (pintype "passive"))
    )
    (net (code "34") (name "Net-(D3-K)") (class "Default")
      (node (ref "C21") (pin "1") (pinfunction "1_1") (pintype "passive"))
      (node (ref "D3") (pin "2") (pinfunction "K_2") (pintype "passive"))
      (node (ref "L2") (pin "1") (pinfunction "1_1") (pintype "passive"))
      (node (ref "U2") (pin "1") (pinfunction "SW_1") (pintype "passive"))
    )
    (net (code "35") (name "Net-(D4-K)") (class "Default")
      (node (ref "C22") (pin "1") (pinfunction "1_1") (pintype "passive"))
      (node (ref "D4") (pin "2") (pinfunction "K_2") (pintype "passive"))
      (node (ref "L3") (pin "1") (pinfunction "1_1") (pintype "passive"))
      (node (ref "U3") (pin "1") (pinfunction "SW_1") (pintype "passive"))
    )
    (net (code "36") (name "Net-(D5-A)") (class "Default")
      (node (ref "C23") (pin "1") (pinfunction "1_1") (pintype "passive"))
      (node (ref "D5") (pin "1") (pinfunction "A_1") (pintype "passive"))
      (node (ref "D6") (pin "1") (pinfunction "A_1") (pintype "passive"))
      (node (ref "U4") (pin "19") (pinfunction "INTVCC_19") (pintype "passive"))
    )
    (net (code "37") (name "Net-(D5-K)") (class "Default")
      (node (ref "C36") (pin "1") (pinfunction "1_1") (pintype "passive"))
      (node (ref "D5") (pin "2") (pinfunction "K_2") (pintype "passive"))
      (node (ref "U4") (pin "24") (pinfunction "BOOST1_24") (pintype "passive"))
    )
    (net (code "38") (name "Net-(D6-K)") (class "Default")
      (node (ref "C37") (pin "1") (pinfunction "1_1") (pintype "passive"))
      (node (ref "D6") (pin "2") (pinfunction "K_2") (pintype "passive"))
      (node (ref "U4") (pin "13") (pinfunction "BOOST2_13") (pintype "passive"))
    )
    (net (code "39") (name "Net-(D7-A)") (class "Default")
      (node (ref "D7") (pin "1") (pinfunction "A_1") (pintype "passive"))
      (node (ref "Q2") (pin "3") (pinfunction "SOURCE_3") (pintype "passive"))
      (node (ref "Q7") (pin "3") (pinfunction "SOURCE_3") (pintype "passive"))
      (node (ref "R32") (pin "2") (pinfunction "2_2") (pintype "passive"))
      (node (ref "R34") (pin "2") (pinfunction "2_2") (pintype "passive"))
    )
    (net (code "40") (name "Net-(D7-K)") (class "Default")
      (node (ref "C37") (pin "2") (pinfunction "2_2") (pintype "passive"))
      (node (ref "D7") (pin "2") (pinfunction "K_2") (pintype "passive"))
      (node (ref "L4") (pin "1") (pinfunction "1_1") (pintype "passive"))
      (node (ref "Q2") (pin "2") (pinfunction "DRAIN_2") (pintype "passive"))
      (node (ref "Q3") (pin "3") (pinfunction "SOURCE_3") (pintype "passive"))
      (node (ref "U4") (pin "15") (pinfunction "SW2_15") (pintype "passive"))
    )
    (net (code "41") (name "Net-(D8-A)") (class "Default")
      (node (ref "C36") (pin "2") (pinfunction "2_2") (pintype "passive"))
      (node (ref "D8") (pin "1") (pinfunction "A_1") (pintype "passive"))
      (node (ref "L4") (pin "2") (pinfunction "2_2") (pintype "passive"))
      (node (ref "Q6") (pin "3") (pinfunction "SOURCE_3") (pintype "passive"))
      (node (ref "Q7") (pin "2") (pinfunction "DRAIN_2") (pintype "passive"))
      (node (ref "U4") (pin "22") (pinfunction "SW1_22") (pintype "passive"))
    )
    (net (code "42") (name "Net-(D9-K)") (class "Default")
      (node (ref "C44") (pin "2") (pinfunction "2_2") (pintype "passive"))
      (node (ref "C45") (pin "2") (pinfunction "2_2") (pintype "passive"))
      (node (ref "D9") (pin "2") (pinfunction "K_2") (pintype "passive"))
      (node (ref "R39") (pin "1") (pinfunction "1_1") (pintype "passive"))
      (node (ref "U6") (pin "5") (pinfunction "VS_5") (pintype "passive"))
    )
    (net (code "43") (name "Net-(D10-K)") (class "Default")
      (node (ref "C46") (pin "1") (pinfunction "1_1") (pintype "passive"))
      (node (ref "C48") (pin "1") (pinfunction "1_1") (pintype "passive"))
      (node (ref "D10") (pin "2") (pinfunction "K_2") (pintype "passive"))
      (node (ref "D12") (pin "2") (pinfunction "K_2") (pintype "passive"))
      (node (ref "R46") (pin "2") (pinfunction "2_2") (pintype "passive"))
      (node (ref "U7") (pin "7") (pinfunction "VCC_7") (pintype "passive"))
    )
    (net (code "44") (name "Net-(D11-A)") (class "Default")
      (node (ref "D11") (pin "1") (pinfunction "A_1") (pintype "passive"))
      (node (ref "Q9") (pin "1") (pinfunction "GATE_1") (pintype "passive"))
      (node (ref "R48") (pin "1") (pinfunction "1_1") (pintype "passive"))
      (node (ref "R51") (pin "1") (pinfunction "1_1") (pintype "passive"))
    )
    (net (code "45") (name "Net-(D11-K)") (class "Default")
      (node (ref "D11") (pin "2") (pinfunction "K_2") (pintype "passive"))
      (node (ref "R48") (pin "2") (pinfunction "2_2") (pintype "passive"))
      (node (ref "U7") (pin "6") (pinfunction "OUT_6") (pintype "passive"))
    )
    (net (code "46") (name "Net-(D12-A)") (class "Default")
      (node (ref "D12") (pin "1") (pinfunction "A_1") (pintype "passive"))
      (node (ref "R52") (pin "2") (pinfunction "2_2") (pintype "passive"))
    )
    (net (code "47") (name "Net-(D13-A)") (class "Default")
      (node (ref "D13") (pin "1") (pinfunction "A_1") (pintype "passive"))
      (node (ref "L5") (pin "2") (pinfunction "2_2") (pintype "passive"))
      (node (ref "Q9") (pin "2") (pinfunction "DRAIN_2") (pintype "passive"))
    )
    (net (code "48") (name "Net-(D13-K)") (class "Default")
      (node (ref "C52") (pin "2") (pinfunction "2_2") (pintype "passive"))
      (node (ref "D13") (pin "2") (pinfunction "K_2") (pintype "passive"))
      (node (ref "R50") (pin "2") (pinfunction "2_2") (pintype "passive"))
      (node (ref "R53") (pin "2") (pinfunction "2_2") (pintype "passive"))
    )
    (net (code "49") (name "Net-(D14-K)") (class "Default")
      (node (ref "D14") (pin "2") (pinfunction "K_2") (pintype "passive"))
      (node (ref "Q10") (pin "1") (pinfunction "GATE_1") (pintype "passive"))
      (node (ref "R56") (pin "2") (pinfunction "2_2") (pintype "passive"))
      (node (ref "R58") (pin "1") (pinfunction "1_1") (pintype "passive"))
    )
    (net (code "50") (name "Net-(D15-A)") (class "Default")
      (node (ref "D15") (pin "1") (pinfunction "A_1") (pintype "passive"))
      (node (ref "Q11") (pin "1") (pinfunction "GATE_1") (pintype "passive"))
      (node (ref "R57") (pin "2") (pinfunction "2_2") (pintype "passive"))
      (node (ref "R59") (pin "2") (pinfunction "2_2") (pintype "passive"))
    )
    (net (code "51") (name "Net-(L5-Pad4)") (class "Default")
      (node (ref "L5") (pin "4") (pinfunction "4_4") (pintype "passive"))
      (node (ref "R52") (pin "1") (pinfunction "1_1") (pintype "passive"))
    )
    (net (code "52") (name "Net-(Q1-B)") (class "Default")
      (node (ref "Q1") (pin "1") (pinfunction "B_1") (pintype "passive"))
      (node (ref "R29") (pin "1") (pinfunction "1_1") (pintype "passive"))
    )
    (net (code "53") (name "Net-(Q1-C)") (class "Default")
      (node (ref "C32") (pin "2") (pinfunction "2_2") (pintype "passive"))
      (node (ref "C35") (pin "2") (pinfunction "2_2") (pintype "passive"))
      (node (ref "L3") (pin "2") (pinfunction "2_2") (pintype "passive"))
      (node (ref "Q1") (pin "2") (pinfunction "C_2") (pintype "passive"))
      (node (ref "R25") (pin "1") (pinfunction "1_1") (pintype "passive"))
    )
    (net (code "54") (name "Net-(Q2-GATE)") (class "Default")
      (node (ref "Q2") (pin "1") (pinfunction "GATE_1") (pintype "passive"))
      (node (ref "U4") (pin "16") (pinfunction "BG2_16") (pintype "passive"))
    )
    (net (code "55") (name "Net-(Q3-GATE)") (class "Default")
      (node (ref "Q3") (pin "1") (pinfunction "GATE_1") (pintype "passive"))
      (node (ref "U4") (pin "14") (pinfunction "TG2_14") (pintype "passive"))
    )
    (net (code "56") (name "Net-(Q4-B)") (class "Default")
      (node (ref "Q4") (pin "1") (pinfunction "B_1") (pintype "passive"))
      (node (ref "R28") (pin "1") (pinfunction "1_1") (pintype "passive"))
    )
    (net (code "57") (name "Net-(Q4-C)") (class "Default")
      (node (ref "C31") (pin "2") (pinfunction "2_2") (pintype "passive"))
      (node (ref "C34") (pin "2") (pinfunction "2_2") (pintype "passive"))
      (node (ref "L2") (pin "2") (pinfunction "2_2") (pintype "passive"))
      (node (ref "Q4") (pin "2") (pinfunction "C_2") (pintype "passive"))
      (node (ref "R23") (pin "1") (pinfunction "1_1") (pintype "passive"))
    )
    (net (code "58") (name "Net-(Q5-B)") (class "Default")
      (node (ref "Q5") (pin "1") (pinfunction "B_1") (pintype "passive"))
      (node (ref "R27") (pin "1") (pinfunction "1_1") (pintype "passive"))
    )
    (net (code "59") (name "Net-(Q5-C)") (class "Default")
      (node (ref "C30") (pin "2") (pinfunction "2_2") (pintype "passive"))
      (node (ref "C33") (pin "2") (pinfunction "2_2") (pintype "passive"))
      (node (ref "L1") (pin "2") (pinfunction "2_2") (pintype "passive"))
      (node (ref "Q5") (pin "2") (pinfunction "C_2") (pintype "passive"))
      (node (ref "R21") (pin "1") (pinfunction "1_1") (pintype "passive"))
    )
    (net (code "60") (name "Net-(Q6-GATE)") (class "Default")
      (node (ref "Q6") (pin "1") (pinfunction "GATE_1") (pintype "passive"))
      (node (ref "U4") (pin "23") (pinfunction "TG1_23") (pintype "passive"))
    )
    (net (code "61") (name "Net-(Q7-GATE)") (class "Default")
      (node (ref "Q7") (pin "1") (pinfunction "GATE_1") (pintype "passive"))
      (node (ref "U4") (pin "18") (pinfunction "BG1_18") (pintype "passive"))
    )
    (net (code "62") (name "Net-(Q8-C)") (class "Default")
      (node (ref "Q8") (pin "3") (pinfunction "C_3") (pintype "passive"))
      (node (ref "R57") (pin "1") (pinfunction "1_1") (pintype "passive"))
    )
    (net (code "63") (name "Net-(Q9-SOURCE)") (class "Default")
      (node (ref "Q9") (pin "3") (pinfunction "SOURCE_3") (pintype "passive"))
      (node (ref "R49") (pin "2") (pinfunction "2_2") (pintype "passive"))
      (node (ref "R54") (pin "1") (pinfunction "1_1") (pintype "passive"))
      (node (ref "R55") (pin "1") (pinfunction "1_1") (pintype "passive"))
    )
    (net (code "64") (name "Net-(Q10-DRAIN)") (class "Default")
      (node (ref "J3") (pin "7") (pinfunction "7_7") (pintype "passive"))
      (node (ref "Q10") (pin "2") (pinfunction "DRAIN_2") (pintype "passive"))
    )
    (net (code "65") (name "Net-(Q11-DRAIN)") (class "Default")
      (node (ref "J3") (pin "4") (pinfunction "4_4") (pintype "passive"))
      (node (ref "Q11") (pin "2") (pinfunction "DRAIN_2") (pintype "passive"))
    )
    (net (code "66") (name "Net-(R45-Pad2)") (class "Default")
      (node (ref "R45") (pin "2") (pinfunction "2_2") (pintype "passive"))
      (node (ref "R46") (pin "1") (pinfunction "1_1") (pintype "passive"))
    )
    (net (code "67") (name "Net-(R47-Pad2)") (class "Default")
      (node (ref "R47") (pin "2") (pinfunction "2_2") (pintype "passive"))
      (node (ref "U8") (pin "1") (pinfunction "1_1") (pintype "passive"))
    )
    (net (code "68") (name "Net-(R56-Pad1)") (class "Default")
      (node (ref "R56") (pin "1") (pinfunction "1_1") (pintype "passive"))
      (node (ref "U8") (pin "3") (pinfunction "3_3") (pintype "passive"))
    )
    (net (code "69") (name "Net-(R62-Pad2)") (class "Default")
      (node (ref "R62") (pin "2") (pinfunction "2_2") (pintype "passive"))
      (node (ref "R63") (pin "1") (pinfunction "1_1") (pintype "passive"))
      (node (ref "U9") (pin "1") (pinfunction "1_1") (pintype "passive"))
    )
    (net (code "70") (name "Net-(U1-BST)") (class "Default")
      (node (ref "C20") (pin "2") (pinfunction "2_2") (pintype "passive"))
      (node (ref "U1") (pin "8") (pinfunction "BST_8") (pintype "passive"))
    )
    (net (code "71") (name "Net-(U1-COMP)") (class "Default")
      (node (ref "C16") (pin "2") (pinfunction "2_2") (pintype "passive"))
      (node (ref "U1") (pin "3") (pinfunction "COMP_3") (pintype "passive"))
    )
    (net (code "72") (name "Net-(U1-FB)") (class "Default")
      (node (ref "R21") (pin "2") (pinfunction "2_2") (pintype "passive"))
      (node (ref "R22") (pin "1") (pinfunction "1_1") (pintype "passive"))
      (node (ref "U1") (pin "4") (pinfunction "FB_4") (pintype "passive"))
    )
    (net (code "73") (name "Net-(U1-FREQ)") (class "Default")
      (node (ref "R4") (pin "1") (pinfunction "1_1") (pintype "passive"))
      (node (ref "U1") (pin "6") (pinfunction "FREQ_6") (pintype "passive"))
    )
    (net (code "74") (name "Net-(U2-BST)") (class "Default")
      (node (ref "C21") (pin "2") (pinfunction "2_2") (pintype "passive"))
      (node (ref "U2") (pin "8") (pinfunction "BST_8") (pintype "passive"))
    )
    (net (code "75") (name "Net-(U2-COMP)") (class "Default")
      (node (ref "C17") (pin "2") (pinfunction "2_2") (pintype "passive"))
      (node (ref "U2") (pin "3") (pinfunction "COMP_3") (pintype "passive"))
    )
    (net (code "76") (name "Net-(U2-FB)") (class "Default")
      (node (ref "R23") (pin "2") (pinfunction "2_2") (pintype "passive"))
      (node (ref "R24") (pin "1") (pinfunction "1_1") (pintype "passive"))
      (node (ref "U2") (pin "4") (pinfunction "FB_4") (pintype "passive"))
    )
    (net (code "77") (name "Net-(U2-FREQ)") (class "Default")
      (node (ref "R5") (pin "1") (pinfunction "1_1") (pintype "passive"))
      (node (ref "U2") (pin "6") (pinfunction "FREQ_6") (pintype "passive"))
    )
    (net (code "78") (name "Net-(U3-BST)") (class "Default")
      (node (ref "C22") (pin "2") (pinfunction "2_2") (pintype "passive"))
      (node (ref "U3") (pin "8") (pinfunction "BST_8") (pintype "passive"))
    )
    (net (code "79") (name "Net-(U3-COMP)") (class "Default")
      (node (ref "C18") (pin "2") (pinfunction "2_2") (pintype "passive"))
      (node (ref "U3") (pin "3") (pinfunction "COMP_3") (pintype "passive"))
    )
    (net (code "80") (name "Net-(U3-FB)") (class "Default")
      (node (ref "R25") (pin "2") (pinfunction "2_2") (pintype "passive"))
      (node (ref "R26") (pin "1") (pinfunction "1_1") (pintype "passive"))
      (node (ref "U3") (pin "4") (pinfunction "FB_4") (pintype "passive"))
    )
    (net (code "81") (name "Net-(U3-FREQ)") (class "Default")
      (node (ref "R6") (pin "1") (pinfunction "1_1") (pintype "passive"))
      (node (ref "U3") (pin "6") (pinfunction "FREQ_6") (pintype "passive"))
    )
    (net (code "82") (name "Net-(U4-ITH)") (class "Default")
      (node (ref "C11") (pin "1") (pinfunction "1_1") (pintype "passive"))
      (node (ref "R7") (pin "2") (pinfunction "2_2") (pintype "passive"))
      (node (ref "U4") (pin "5") (pinfunction "ITH_5") (pintype "passive"))
    )
    (net (code "83") (name "Net-(U4-PLLFLTR)") (class "Default")
      (node (ref "R2") (pin "1") (pinfunction "1_1") (pintype "passive"))
      (node (ref "R3") (pin "2") (pinfunction "2_2") (pintype "passive"))
      (node (ref "U4") (pin "10") (pinfunction "PLLFLTR_10") (pintype "passive"))
    )
    (net (code "84") (name "Net-(U4-SENSE+)") (class "Default")
      (node (ref "C38") (pin "1") (pinfunction "1_1") (pintype "passive"))
      (node (ref "R32") (pin "1") (pinfunction "1_1") (pintype "passive"))
      (node (ref "U4") (pin "3") (pinfunction "SENSE+_3") (pintype "passive"))
    )
    (net (code "85") (name "Net-(U4-SENSE-)") (class "Default")
      (node (ref "C38") (pin "2") (pinfunction "2_2") (pintype "passive"))
      (node (ref "R33") (pin "1") (pinfunction "1_1") (pintype "passive"))
      (node (ref "U4") (pin "4") (pinfunction "SENSE-_4") (pintype "passive"))
    )
    (net (code "86") (name "Net-(U4-SS)") (class "Default")
      (node (ref "C15") (pin "1") (pinfunction "1_1") (pintype "passive"))
      (node (ref "U4") (pin "2") (pinfunction "SS_2") (pintype "passive"))
    )
    (net (code "87") (name "Net-(U4-STBYMD)") (class "Default")
      (node (ref "C13") (pin "1") (pinfunction "1_1") (pintype "passive"))
      (node (ref "U4") (pin "12") (pinfunction "STBYMD_12") (pintype "passive"))
    )
    (net (code "88") (name "Net-(U4-VIN)") (class "Default")
      (node (ref "C19") (pin "1") (pinfunction "1_1") (pintype "passive"))
      (node (ref "R12") (pin "1") (pinfunction "1_1") (pintype "passive"))
      (node (ref "U4") (pin "21") (pinfunction "VIN_21") (pintype "passive"))
    )
    (net (code "89") (name "Net-(U4-VOSENSE)") (class "Default")
      (node (ref "R30") (pin "2") (pinfunction "2_2") (pintype "passive"))
      (node (ref "R31") (pin "1") (pinfunction "1_1") (pintype "passive"))
      (node (ref "U4") (pin "6") (pinfunction "VOSENSE_6") (pintype "passive"))
    )
    (net (code "90") (name "Net-(U5A-INA+)") (class "Default")
      (node (ref "C10") (pin "2") (pinfunction "2_2") (pintype "passive"))
      (node (ref "R8") (pin "2") (pinfunction "2_2") (pintype "passive"))
      (node (ref "U5") (pin "3") (pinfunction "INA+_3") (pintype "passive"))
    )
    (net (code "91") (name "Net-(U5A-INA-)") (class "Default")
      (node (ref "C24") (pin "2") (pinfunction "2_2") (pintype "passive"))
      (node (ref "C29") (pin "2") (pinfunction "2_2") (pintype "passive"))
      (node (ref "R18") (pin "1") (pinfunction "1_1") (pintype "passive"))
      (node (ref "U5") (pin "2") (pinfunction "INA-_2") (pintype "passive"))
    )
    (net (code "92") (name "Net-(U5A-OUTA)") (class "Default")
      (node (ref "C29") (pin "1") (pinfunction "1_1") (pintype "passive"))
      (node (ref "R27") (pin "2") (pinfunction "2_2") (pintype "passive"))
      (node (ref "U5") (pin "1") (pinfunction "OUTA_1") (pintype "passive"))
    )
    (net (code "93") (name "Net-(U5B-INB+)") (class "Default")
      (node (ref "C12") (pin "2") (pinfunction "2_2") (pintype "passive"))
      (node (ref "R9") (pin "2") (pinfunction "2_2") (pintype "passive"))
      (node (ref "U5") (pin "5") (pinfunction "INB+_5") (pintype "passive"))
    )
    (net (code "94") (name "Net-(U5B-INB-)") (class "Default")
      (node (ref "C25") (pin "2") (pinfunction "2_2") (pintype "passive"))
      (node (ref "C27") (pin "1") (pinfunction "1_1") (pintype "passive"))
      (node (ref "R19") (pin "1") (pinfunction "1_1") (pintype "passive"))
      (node (ref "U5") (pin "6") (pinfunction "INB-_6") (pintype "passive"))
    )
    (net (code "95") (name "Net-(U5B-OUTB)") (class "Default")
      (node (ref "C27") (pin "2") (pinfunction "2_2") (pintype "passive"))
      (node (ref "R28") (pin "2") (pinfunction "2_2") (pintype "passive"))
      (node (ref "U5") (pin "7") (pinfunction "OUTB_7") (pintype "passive"))
    )
    (net (code "96") (name "Net-(U5D-IND+)") (class "Default")
      (node (ref "C14") (pin "2") (pinfunction "2_2") (pintype "passive"))
      (node (ref "R10") (pin "2") (pinfunction "2_2") (pintype "passive"))
      (node (ref "U5") (pin "12") (pinfunction "IND+_12") (pintype "passive"))
    )
    (net (code "97") (name "Net-(U5D-IND-)") (class "Default")
      (node (ref "C26") (pin "2") (pinfunction "2_2") (pintype "passive"))
      (node (ref "C28") (pin "1") (pinfunction "1_1") (pintype "passive"))
      (node (ref "R20") (pin "1") (pinfunction "1_1") (pintype "passive"))
      (node (ref "U5") (pin "13") (pinfunction "IND-_13") (pintype "passive"))
    )
    (net (code "98") (name "Net-(U5D-OUTD)") (class "Default")
      (node (ref "C28") (pin "2") (pinfunction "2_2") (pintype "passive"))
      (node (ref "R29") (pin "2") (pinfunction "2_2") (pintype "passive"))
      (node (ref "U5") (pin "14") (pinfunction "OUTD_14") (pintype "passive"))
    )
    (net (code "99") (name "Net-(U6-IN+)") (class "Default")
      (node (ref "C40") (pin "1") (pinfunction "1_1") (pintype "passive"))
      (node (ref "R40") (pin "2") (pinfunction "2_2") (pintype "passive"))
      (node (ref "U6") (pin "3") (pinfunction "IN+_3") (pintype "passive"))
    )
    (net (code "100") (name "Net-(U6-IN-)") (class "Default")
      (node (ref "C40") (pin "2") (pinfunction "2_2") (pintype "passive"))
      (node (ref "R43") (pin "2") (pinfunction "2_2") (pintype "passive"))
      (node (ref "U6") (pin "4") (pinfunction "IN-_4") (pintype "passive"))
    )
    (net (code "101") (name "Net-(U7-COMP)") (class "Default")
      (node (ref "C42") (pin "2") (pinfunction "2_2") (pintype "passive"))
      (node (ref "R44") (pin "1") (pinfunction "1_1") (pintype "passive"))
      (node (ref "U7") (pin "1") (pinfunction "COMP_1") (pintype "passive"))
      (node (ref "U9") (pin "4") (pinfunction "4_4") (pintype "passive"))
    )
    (net (code "102") (name "Net-(U7-Isns)") (class "Default")
      (node (ref "C43") (pin "2") (pinfunction "2_2") (pintype "passive"))
      (node (ref "C47") (pin "1") (pinfunction "1_1") (pintype "passive"))
      (node (ref "R49") (pin "1") (pinfunction "1_1") (pintype "passive"))
      (node (ref "U7") (pin "3") (pinfunction "Isns_3") (pintype "passive"))
    )
    (net (code "103") (name "Net-(U7-RtCt)") (class "Default")
      (node (ref "C41") (pin "1") (pinfunction "1_1") (pintype "passive"))
      (node (ref "C43") (pin "1") (pinfunction "1_1") (pintype "passive"))
      (node (ref "R42") (pin "1") (pinfunction "1_1") (pintype "passive"))
      (node (ref "U7") (pin "4") (pinfunction "RtCt_4") (pintype "passive"))
    )
    (net (code "104") (name "Net-(U7-Vref)") (class "Default")
      (node (ref "C39") (pin "1") (pinfunction "1_1") (pintype "passive"))
      (node (ref "R42") (pin "2") (pinfunction "2_2") (pintype "passive"))
      (node (ref "U7") (pin "8") (pinfunction "Vref_8") (pintype "passive"))
    )
    (net (code "105") (name "Net-(U10-C)") (class "Default")
      (node (ref "R63") (pin "2") (pinfunction "2_2") (pintype "passive"))
      (node (ref "R64") (pin "1") (pinfunction "1_1") (pintype "passive"))
      (node (ref "U10") (pin "2") (pinfunction "C_2") (pintype "passive"))
      (node (ref "U9") (pin "2") (pinfunction "2_2") (pintype "passive"))
    )
    (net (code "106") (name "Net-(U10-REF)") (class "Default")
      (node (ref "C67") (pin "1") (pinfunction "1_1") (pintype "passive"))
      (node (ref "R65") (pin "2") (pinfunction "2_2") (pintype "passive"))
      (node (ref "R66") (pin "1") (pinfunction "1_1") (pintype "passive"))
      (node (ref "U10") (pin "1") (pinfunction "REF_1") (pintype "passive"))
    )
    (net (code "107") (name "Vin") (class "Default")
      (node (ref "C49") (pin "2") (pinfunction "2_2") (pintype "passive"))
      (node (ref "C53") (pin "2") (pinfunction "2_2") (pintype "passive"))
      (node (ref "C56") (pin "1") (pinfunction "1_1") (pintype "passive"))
      (node (ref "C60") (pin "1") (pinfunction "1_1") (pintype "passive"))
      (node (ref "C63") (pin "1") (pinfunction "1_1") (pintype "passive"))
      (node (ref "DN1") (pin "1") (pinfunction "1_1") (pintype "passive"))
      (node (ref "Q3") (pin "2") (pinfunction "DRAIN_2") (pintype "passive"))
      (node (ref "R1") (pin "2") (pinfunction "2_2") (pintype "passive"))
      (node (ref "R12") (pin "2") (pinfunction "2_2") (pintype "passive"))
      (node (ref "R35") (pin "1") (pinfunction "1_1") (pintype "passive"))
    )
    (net (code "108") (name "X+") (class "Default")
      (node (ref "J1") (pin "19") (pinfunction "19_19") (pintype "passive"))
      (node (ref "J3") (pin "10") (pinfunction "10_10") (pintype "passive"))
    )
    (net (code "109") (name "X-") (class "Default")
      (node (ref "J1") (pin "20") (pinfunction "20_20") (pintype "passive"))
      (node (ref "J3") (pin "9") (pinfunction "9_9") (pintype "passive"))
    )
    (net (code "110") (name "Y+") (class "Default")
      (node (ref "J1") (pin "18") (pinfunction "18_18") (pintype "passive"))
      (node (ref "J3") (pin "1") (pinfunction "1_1") (pintype "passive"))
    )
    (net (code "111") (name "Y-") (class "Default")
      (node (ref "J1") (pin "17") (pinfunction "17_17") (pintype "passive"))
      (node (ref "J3") (pin "2") (pinfunction "2_2") (pintype "passive"))
    )
    (net (code "112") (name "unconnected-(J2-Pad1)") (class "Default")
      (node (ref "J2") (pin "1") (pinfunction "1_1") (pintype "passive"))
    )
    (net (code "113") (name "unconnected-(J2-Pad2)") (class "Default")
      (node (ref "J2") (pin "2") (pinfunction "2_2") (pintype "passive"))
    )
    (net (code "114") (name "unconnected-(J2-Pad3)") (class "Default")
      (node (ref "J2") (pin "3") (pinfunction "3_3") (pintype "passive"))
    )
    (net (code "115") (name "unconnected-(J2-Pad4)") (class "Default")
      (node (ref "J2") (pin "4") (pinfunction "4_4") (pintype "passive"))
    )
    (net (code "116") (name "unconnected-(J2-Pad5)") (class "Default")
      (node (ref "J2") (pin "5") (pinfunction "5_5") (pintype "passive"))
    )
    (net (code "117") (name "unconnected-(J2-Pad6)") (class "Default")
      (node (ref "J2") (pin "6") (pinfunction "6_6") (pintype "passive"))
    )
    (net (code "118") (name "unconnected-(J2-Pad7)") (class "Default")
      (node (ref "J2") (pin "7") (pinfunction "7_7") (pintype "passive"))
    )
    (net (code "119") (name "unconnected-(J2-Pad8)") (class "Default")
      (node (ref "J2") (pin "8") (pinfunction "8_8") (pintype "passive"))
    )
    (net (code "120") (name "unconnected-(J2-Pad9)") (class "Default")
      (node (ref "J2") (pin "9") (pinfunction "9_9") (pintype "passive"))
    )
    (net (code "121") (name "unconnected-(J2-Pad10)") (class "Default")
      (node (ref "J2") (pin "10") (pinfunction "10_10") (pintype "passive"))
    )
    (net (code "122") (name "unconnected-(J2-Pad11)") (class "Default")
      (node (ref "J2") (pin "11") (pinfunction "11_11") (pintype "passive"))
    )
    (net (code "123") (name "unconnected-(J2-Pad12)") (class "Default")
      (node (ref "J2") (pin "12") (pinfunction "12_12") (pintype "passive"))
    )
    (net (code "124") (name "unconnected-(J2-Pad13)") (class "Default")
      (node (ref "J2") (pin "13") (pinfunction "13_13") (pintype "passive"))
    )
    (net (code "125") (name "unconnected-(J2-Pad14)") (class "Default")
      (node (ref "J2") (pin "14") (pinfunction "14_14") (pintype "passive"))
    )
    (net (code "126") (name "unconnected-(U5C-OUTC-Pad8)") (class "Default")
      (node (ref "U5") (pin "8") (pinfunction "OUTC_8") (pintype "passive+no_connect"))
    )
  )
)
